# STM32G4_microcontroller_Power.net
KiCad netlist of a schematic drawn in Altium Designer
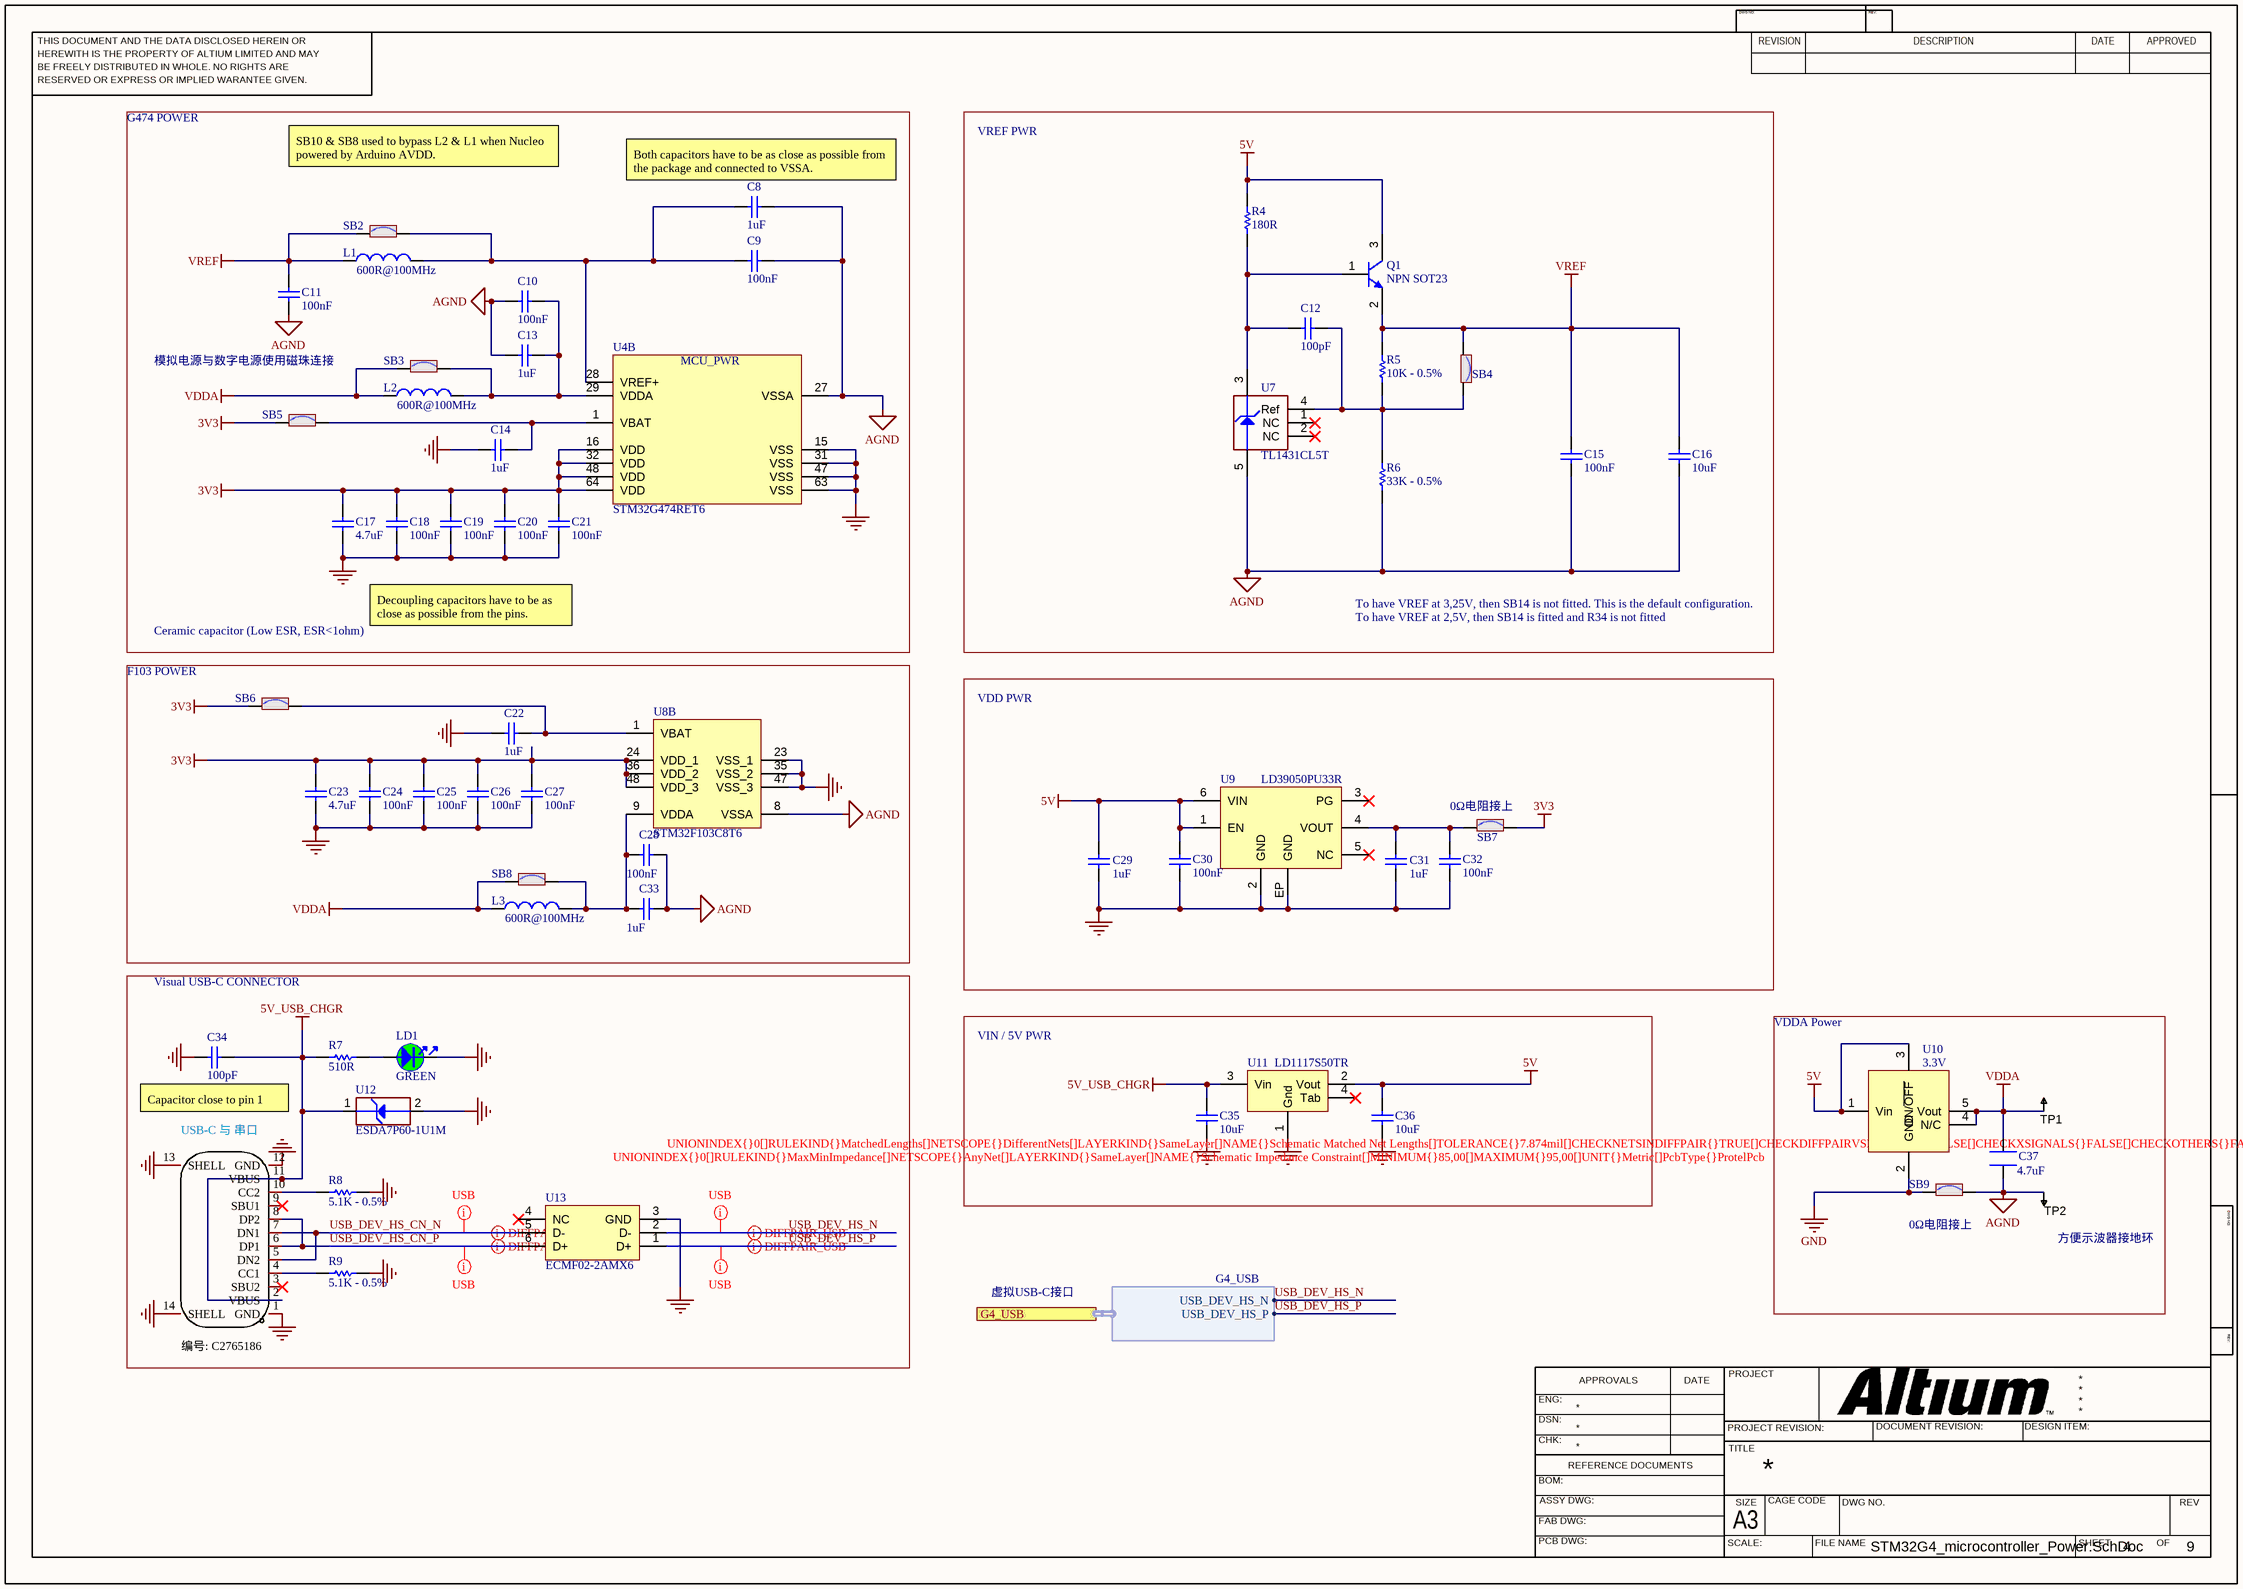
[diagram p0: STM32G4_microcontroller_Power.SchDoc]

(export (version "E")
  (design (tool "Eeschema 10.0.6"))
  (components
    (comp (ref "C8")
      (value "1uF")
      (footprint "C0603")
      (description "Capacitor, MLCC, 1uF, 16V, X5R, 10%, 0603, T=0,8mm")
      (fields
        (field (name "INTERNAL_PART_NUMBER") "MCD-00010")
        (field (name "MANUFACTURER_PART_NUMBER") "CC0603KRX5R7BB105")
        (field (name "PROVIDED_BY") "Subcon")
      )
      (libsource (lib "MCD_PARTS_database") (part "Capacitor"))
    )
    (comp (ref "C9")
      (value "100nF")
      (footprint "C0402")
      (description "Capacitor, MLCC, 100nF, 16V, X7R, 10%, 0402, T=0,5mm")
      (fields
        (field (name "INTERNAL_PART_NUMBER") "MCD-00102")
        (field (name "MANUFACTURER_PART_NUMBER") "CC0402KRX7R7BB104")
        (field (name "PROVIDED_BY") "Subcon")
      )
      (libsource (lib "MCD_PARTS_database") (part "Capacitor"))
    )
    (comp (ref "C10")
      (value "100nF")
      (footprint "C0402")
      (description "Capacitor, MLCC, 100nF, 16V, X7R, 10%, 0402, T=0,5mm")
      (fields
        (field (name "INTERNAL_PART_NUMBER") "MCD-00102")
        (field (name "MANUFACTURER_PART_NUMBER") "CC0402KRX7R7BB104")
        (field (name "PROVIDED_BY") "Subcon")
      )
      (libsource (lib "MCD_PARTS_database") (part "Capacitor"))
    )
    (comp (ref "C11")
      (value "100nF")
      (footprint "C0402")
      (description "Capacitor, MLCC, 100nF, 16V, X7R, 10%, 0402, T=0,5mm")
      (fields
        (field (name "INTERNAL_PART_NUMBER") "MCD-00102")
        (field (name "MANUFACTURER_PART_NUMBER") "CC0402KRX7R7BB104")
        (field (name "PROVIDED_BY") "Subcon")
      )
      (libsource (lib "MCD_PARTS_database") (part "Capacitor"))
    )
    (comp (ref "C12")
      (value "100pF")
      (footprint "C0603")
      (description "Capacitor,100pF,50V,X7R,10%,0603")
      (fields
        (field (name "INTERNAL_PART_NUMBER") "MCD-01101")
        (field (name "MANUFACTURER_PART_NUMBER") "06035C101JAT4A")
        (field (name "PROVIDED_BY") "SUBCO")
      )
      (libsource (lib "MCD_PARTS_database") (part "Capacitor"))
    )
    (comp (ref "C13")
      (value "1uF")
      (footprint "C0603")
      (description "Capacitor, MLCC, 1uF, 16V, X5R, 10%, 0603, T=0,8mm")
      (fields
        (field (name "INTERNAL_PART_NUMBER") "MCD-00010")
        (field (name "MANUFACTURER_PART_NUMBER") "CC0603KRX5R7BB105")
        (field (name "PROVIDED_BY") "Subcon")
      )
      (libsource (lib "MCD_PARTS_database") (part "Capacitor"))
    )
    (comp (ref "C14")
      (value "1uF")
      (footprint "C0603")
      (description "Capacitor, MLCC, 1uF, 16V, X5R, 10%, 0603, T=0,8mm")
      (fields
        (field (name "INTERNAL_PART_NUMBER") "MCD-00010")
        (field (name "MANUFACTURER_PART_NUMBER") "CC0603KRX5R7BB105")
        (field (name "PROVIDED_BY") "Subcon")
      )
      (libsource (lib "MCD_PARTS_database") (part "Capacitor"))
    )
    (comp (ref "C15")
      (value "100nF")
      (footprint "C0603")
      (description "Capacitor, MLCC, 100nF, 16V, X7R, 10%, 0603, T=0,8mm")
      (fields
        (field (name "INTERNAL_PART_NUMBER") "MCD-00211")
        (field (name "MANUFACTURER_PART_NUMBER") "CC0603KRX7R7BB104")
        (field (name "PROVIDED_BY") "SUBCO")
      )
      (libsource (lib "MCD_PARTS_database") (part "Capacitor"))
    )
    (comp (ref "C16")
      (value "10uF")
      (footprint "C0603")
      (description "Capacitor, MLCC, 10uF, 10V, X5R, 10%, 0603, T=0.8mm")
      (fields
        (field (name "INTERNAL_PART_NUMBER") "MCD-01124")
        (field (name "MANUFACTURER_PART_NUMBER") "GRM188R61A106KAAL")
        (field (name "PROVIDED_BY") "SUBCO")
      )
      (libsource (lib "MCD_PARTS_database") (part "Capacitor"))
    )
    (comp (ref "C17")
      (value "4.7uF")
      (footprint "C0603")
      (description "Capacitor, MLCC, 4.7uF, 16V, X5R, 10%, 0603, T=0.8mm")
      (fields
        (field (name "INTERNAL_PART_NUMBER") "MCD-00009")
        (field (name "MANUFACTURER_PART_NUMBER") "CC0603KRX5R7BB475")
        (field (name "PROVIDED_BY") "subcon")
      )
      (libsource (lib "MCD_PARTS_database") (part "Capacitor"))
    )
    (comp (ref "C18")
      (value "100nF")
      (footprint "C0402")
      (description "Capacitor, MLCC, 100nF, 16V, X7R, 10%, 0402, T=0,5mm")
      (fields
        (field (name "INTERNAL_PART_NUMBER") "MCD-00102")
        (field (name "MANUFACTURER_PART_NUMBER") "CC0402KRX7R7BB104")
        (field (name "PROVIDED_BY") "Subcon")
      )
      (libsource (lib "MCD_PARTS_database") (part "Capacitor"))
    )
    (comp (ref "C19")
      (value "100nF")
      (footprint "C0402")
      (description "Capacitor, MLCC, 100nF, 16V, X7R, 10%, 0402, T=0,5mm")
      (fields
        (field (name "INTERNAL_PART_NUMBER") "MCD-00102")
        (field (name "MANUFACTURER_PART_NUMBER") "CC0402KRX7R7BB104")
        (field (name "PROVIDED_BY") "Subcon")
      )
      (libsource (lib "MCD_PARTS_database") (part "Capacitor"))
    )
    (comp (ref "C20")
      (value "100nF")
      (footprint "C0402")
      (description "Capacitor, MLCC, 100nF, 16V, X7R, 10%, 0402, T=0,5mm")
      (fields
        (field (name "INTERNAL_PART_NUMBER") "MCD-00102")
        (field (name "MANUFACTURER_PART_NUMBER") "CC0402KRX7R7BB104")
        (field (name "PROVIDED_BY") "Subcon")
      )
      (libsource (lib "MCD_PARTS_database") (part "Capacitor"))
    )
    (comp (ref "C21")
      (value "100nF")
      (footprint "C0402")
      (description "Capacitor, MLCC, 100nF, 16V, X7R, 10%, 0402, T=0,5mm")
      (fields
        (field (name "INTERNAL_PART_NUMBER") "MCD-00102")
        (field (name "MANUFACTURER_PART_NUMBER") "CC0402KRX7R7BB104")
        (field (name "PROVIDED_BY") "Subcon")
      )
      (libsource (lib "MCD_PARTS_database") (part "Capacitor"))
    )
    (comp (ref "C22")
      (value "1uF")
      (footprint "C0603")
      (description "Capacitor, MLCC, 1uF, 16V, X5R, 10%, 0603, T=0,8mm")
      (fields
        (field (name "INTERNAL_PART_NUMBER") "MCD-00010")
        (field (name "MANUFACTURER_PART_NUMBER") "CC0603KRX5R7BB105")
        (field (name "PROVIDED_BY") "Subcon")
      )
      (libsource (lib "MCD_PARTS_database") (part "Capacitor"))
    )
    (comp (ref "C23")
      (value "4.7uF")
      (footprint "C0603")
      (description "Capacitor, MLCC, 4.7uF, 16V, X5R, 10%, 0603, T=0.8mm")
      (fields
        (field (name "INTERNAL_PART_NUMBER") "MCD-00009")
        (field (name "MANUFACTURER_PART_NUMBER") "CC0603KRX5R7BB475")
        (field (name "PROVIDED_BY") "subcon")
      )
      (libsource (lib "MCD_PARTS_database") (part "Capacitor"))
    )
    (comp (ref "C24")
      (value "100nF")
      (footprint "C0402")
      (description "Capacitor, MLCC, 100nF, 16V, X7R, 10%, 0402, T=0,5mm")
      (fields
        (field (name "INTERNAL_PART_NUMBER") "MCD-00102")
        (field (name "MANUFACTURER_PART_NUMBER") "CC0402KRX7R7BB104")
        (field (name "PROVIDED_BY") "Subcon")
      )
      (libsource (lib "MCD_PARTS_database") (part "Capacitor"))
    )
    (comp (ref "C25")
      (value "100nF")
      (footprint "C0402")
      (description "Capacitor, MLCC, 100nF, 16V, X7R, 10%, 0402, T=0,5mm")
      (fields
        (field (name "INTERNAL_PART_NUMBER") "MCD-00102")
        (field (name "MANUFACTURER_PART_NUMBER") "CC0402KRX7R7BB104")
        (field (name "PROVIDED_BY") "Subcon")
      )
      (libsource (lib "MCD_PARTS_database") (part "Capacitor"))
    )
    (comp (ref "C26")
      (value "100nF")
      (footprint "C0402")
      (description "Capacitor, MLCC, 100nF, 16V, X7R, 10%, 0402, T=0,5mm")
      (fields
        (field (name "INTERNAL_PART_NUMBER") "MCD-00102")
        (field (name "MANUFACTURER_PART_NUMBER") "CC0402KRX7R7BB104")
        (field (name "PROVIDED_BY") "Subcon")
      )
      (libsource (lib "MCD_PARTS_database") (part "Capacitor"))
    )
    (comp (ref "C27")
      (value "100nF")
      (footprint "C0402")
      (description "Capacitor, MLCC, 100nF, 16V, X7R, 10%, 0402, T=0,5mm")
      (fields
        (field (name "INTERNAL_PART_NUMBER") "MCD-00102")
        (field (name "MANUFACTURER_PART_NUMBER") "CC0402KRX7R7BB104")
        (field (name "PROVIDED_BY") "Subcon")
      )
      (libsource (lib "MCD_PARTS_database") (part "Capacitor"))
    )
    (comp (ref "C28")
      (value "100nF")
      (footprint "C0402")
      (description "Capacitor, MLCC, 100nF, 16V, X7R, 10%, 0402, T=0,5mm")
      (fields
        (field (name "INTERNAL_PART_NUMBER") "MCD-00102")
        (field (name "MANUFACTURER_PART_NUMBER") "CC0402KRX7R7BB104")
        (field (name "PROVIDED_BY") "Subcon")
      )
      (libsource (lib "MCD_PARTS_database") (part "Capacitor"))
    )
    (comp (ref "C29")
      (value "1uF")
      (footprint "C0603")
      (description "Capacitor, MLCC, 1uF, 16V, X5R, 10%, 0603, T=0,8mm")
      (fields
        (field (name "INTERNAL_PART_NUMBER") "MCD-00010")
        (field (name "MANUFACTURER_PART_NUMBER") "CC0603KRX5R7BB105")
        (field (name "PROVIDED_BY") "Subcon")
      )
      (libsource (lib "MCD_PARTS_database") (part "Capacitor"))
    )
    (comp (ref "C30")
      (value "100nF")
      (footprint "C0402")
      (description "Capacitor, MLCC, 100nF, 16V, X7R, 10%, 0402, T=0,5mm")
      (fields
        (field (name "INTERNAL_PART_NUMBER") "MCD-00102")
        (field (name "MANUFACTURER_PART_NUMBER") "CC0402KRX7R7BB104")
        (field (name "PROVIDED_BY") "Subcon")
      )
      (libsource (lib "MCD_PARTS_database") (part "Capacitor"))
    )
    (comp (ref "C31")
      (value "1uF")
      (footprint "C0603")
      (description "Capacitor, MLCC, 1uF, 16V, X5R, 10%, 0603, T=0,8mm")
      (fields
        (field (name "INTERNAL_PART_NUMBER") "MCD-00010")
        (field (name "MANUFACTURER_PART_NUMBER") "CC0603KRX5R7BB105")
        (field (name "PROVIDED_BY") "Subcon")
      )
      (libsource (lib "MCD_PARTS_database") (part "Capacitor"))
    )
    (comp (ref "C32")
      (value "100nF")
      (footprint "C0402")
      (description "Capacitor, MLCC, 100nF, 16V, X7R, 10%, 0402, T=0,5mm")
      (fields
        (field (name "INTERNAL_PART_NUMBER") "MCD-00102")
        (field (name "MANUFACTURER_PART_NUMBER") "CC0402KRX7R7BB104")
        (field (name "PROVIDED_BY") "Subcon")
      )
      (libsource (lib "MCD_PARTS_database") (part "Capacitor"))
    )
    (comp (ref "C33")
      (value "1uF")
      (footprint "C0603")
      (description "Capacitor, MLCC, 1uF, 16V, X5R, 10%, 0603, T=0,8mm")
      (fields
        (field (name "INTERNAL_PART_NUMBER") "MCD-00010")
        (field (name "MANUFACTURER_PART_NUMBER") "CC0603KRX5R7BB105")
        (field (name "PROVIDED_BY") "Subcon")
      )
      (libsource (lib "MCD_PARTS_database") (part "Capacitor"))
    )
    (comp (ref "C34")
      (value "100pF")
      (footprint "C0402")
      (description "Capacitor, MLCC, 100pF, 50V, NPO, 5%, 0402, T=0,5mm")
      (fields
        (field (name "INTERNAL_PART_NUMBER") "MCD-00205")
        (field (name "MANUFACTURER_PART_NUMBER") "CC0402JRNPO9BN101")
        (field (name "PROVIDED_BY") "Subcon")
      )
      (libsource (lib "MCD_PARTS_database") (part "Capacitor"))
    )
    (comp (ref "C35")
      (value "10uF")
      (footprint "C0805")
      (description "Capacitor, MLCC, 10uF, 25V, X5R, 10%, 0805, T=0,85mm")
      (fields
        (field (name "INTERNAL_PART_NUMBER") "MCD-00014")
        (field (name "MANUFACTURER_PART_NUMBER") "CC0805KRX5R8BB106")
        (field (name "PROVIDED_BY") "SUBCO")
      )
      (libsource (lib "MCD_PARTS_database") (part "Capacitor"))
    )
    (comp (ref "C36")
      (value "10uF")
      (footprint "C0805")
      (description "Capacitor, MLCC, 10uF, 25V, X5R, 10%, 0805, T=0,85mm")
      (fields
        (field (name "INTERNAL_PART_NUMBER") "MCD-00014")
        (field (name "MANUFACTURER_PART_NUMBER") "CC0805KRX5R8BB106")
        (field (name "PROVIDED_BY") "SUBCO")
      )
      (libsource (lib "MCD_PARTS_database") (part "Capacitor"))
    )
    (comp (ref "C37")
      (value "4.7uF")
      (footprint "CAPC2012X09N")
      (description "CAP CER 4.7UF 35V X5R 0805")
      (fields
        (field (name "MANUFACTURER") "Murata Electronics North America")
        (field (name "TOLERANCE") "±10%")
      )
      (libsource (lib "CustomComponents") (part "GRM219R6YA475KA73D"))
    )
    (comp (ref "L1")
      (value "600R@100MHz")
      (footprint "L0603")
      (description "SMD Chip ferrite bead, 600R@100MHz +/-25%, 350mA, 500mohm DC, 0603, T=0.8mm")
      (fields
        (field (name "INTERNAL_PART_NUMBER") "MCD-00047")
        (field (name "MANUFACTURER_PART_NUMBER") "FCM1608KF-601T03")
        (field (name "PROVIDED_BY") "SUBCO")
      )
      (libsource (lib "MCD_PARTS_database") (part "BEAD"))
    )
    (comp (ref "L2")
      (value "600R@100MHz")
      (footprint "L0603")
      (description "SMD Chip ferrite bead, 600R@100MHz +/-25%, 350mA, 500mohm DC, 0603, T=0.8mm")
      (fields
        (field (name "INTERNAL_PART_NUMBER") "MCD-00047")
        (field (name "MANUFACTURER_PART_NUMBER") "FCM1608KF-601T03")
        (field (name "PROVIDED_BY") "SUBCO")
      )
      (libsource (lib "MCD_PARTS_database") (part "BEAD"))
    )
    (comp (ref "L3")
      (value "600R@100MHz")
      (footprint "L0603")
      (description "SMD Chip ferrite bead, 600R@100MHz +/-25%, 350mA, 500mohm DC, 0603, T=0.8mm")
      (fields
        (field (name "INTERNAL_PART_NUMBER") "MCD-00047")
        (field (name "MANUFACTURER_PART_NUMBER") "FCM1608KF-601T03")
        (field (name "PROVIDED_BY") "SUBCO")
      )
      (libsource (lib "MCD_PARTS_database") (part "BEAD"))
    )
    (comp (ref "LD1")
      (value "GREEN")
      (footprint "LED_0603_GREEN")
      (description "LED, Green, 0603")
      (fields
        (field (name "INTERNAL_PART_NUMBER") "MCD-00050")
        (field (name "MANUFACTURER_PART_NUMBER") "19-213SYGC/S530-E2/TR8")
        (field (name "PROVIDED_BY") "SUBCO")
      )
      (libsource (lib "MCD_PARTS_database") (part "LED_green"))
    )
    (comp (ref "Q1")
      (value "NPN SOT23")
      (footprint "NPN_SOT23")
      (description "NPN Bipolar Transistor")
      (fields
        (field (name "INTERNAL_PART_NUMBER") "MCD-00073")
        (field (name "MANUFACTURER_PART_NUMBER") "BSR14")
        (field (name "PROVIDED_BY") "SUBCO")
      )
      (libsource (lib "MCD_PARTS_database") (part "9013-SOT23"))
    )
    (comp (ref "R4")
      (value "180R")
      (footprint "R0603")
      (description "Resistor,180R,0603,1%,1/10W")
      (fields
        (field (name "INTERNAL_PART_NUMBER") "MCD-00342")
        (field (name "MANUFACTURER_PART_NUMBER") "RC0603FR-07180RL")
        (field (name "PROVIDED_BY") "SUBCO")
      )
      (libsource (lib "MCD_PARTS_database") (part "Resistor"))
    )
    (comp (ref "R5")
      (value "10K - 0.5%")
      (footprint "R0603")
      (description "resistor, 10K, 0603, 0.5%, 1/10W")
      (fields
        (field (name "INTERNAL_PART_NUMBER") "MCD-01215")
        (field (name "MANUFACTURER_PART_NUMBER") "RC0603DR-0710KL")
        (field (name "PROVIDED_BY") "SUBCO")
      )
      (libsource (lib "MCD_PARTS_database") (part "Resistor"))
    )
    (comp (ref "R6")
      (value "33K - 0.5%")
      (footprint "R0603")
      (description "Resistor,33K,0603,0.5%,1/10W")
      (fields
        (field (name "INTERNAL_PART_NUMBER") "MCD-01209")
        (field (name "MANUFACTURER_PART_NUMBER") "RC0603DR-0733KL")
        (field (name "PROVIDED_BY") "SUBCO")
      )
      (libsource (lib "MCD_PARTS_database") (part "Resistor"))
    )
    (comp (ref "R7")
      (value "510R")
      (footprint "R0603")
      (description "Resistor,510R,0603,1%,1/10W")
      (fields
        (field (name "INTERNAL_PART_NUMBER") "MCD-00225")
        (field (name "MANUFACTURER_PART_NUMBER") "RC0603FR-07510RL")
        (field (name "PROVIDED_BY") "SUBCO")
      )
      (libsource (lib "MCD_PARTS_database") (part "Resistor"))
    )
    (comp (ref "R8")
      (value "5.1K - 0.5%")
      (footprint "R0603")
      (description "Resistor,5.1K,0603,0.5%,1/10W")
      (fields
        (field (name "INTERNAL_PART_NUMBER") "MCD-01209")
        (field (name "MANUFACTURER_PART_NUMBER") "RC0603DR-0733KL")
        (field (name "PROVIDED_BY") "SUBCO")
      )
      (libsource (lib "MCD_PARTS_database") (part "Resistor"))
    )
    (comp (ref "R9")
      (value "5.1K - 0.5%")
      (footprint "R0603")
      (description "Resistor,5.1K,0603,0.5%,1/10W")
      (fields
        (field (name "INTERNAL_PART_NUMBER") "MCD-01209")
        (field (name "MANUFACTURER_PART_NUMBER") "RC0603DR-0733KL")
        (field (name "PROVIDED_BY") "SUBCO")
      )
      (libsource (lib "MCD_PARTS_database") (part "Resistor"))
    )
    (comp (ref "SB2")
      (value "~")
      (footprint "SOLDER-BRIDGE_R0603-0R")
      (description "Solder Bridge ON")
      (fields
        (field (name "INTERNAL_PART_NUMBER") "MCD-00071")
        (field (name "MANUFACTURER_PART_NUMBER") "RC0603JR-070RL")
        (field (name "PROVIDED_BY") "SUBCO")
      )
      (libsource (lib "MCD_PARTS_database") (part "SB_ON"))
    )
    (comp (ref "SB3")
      (value "~")
      (footprint "SOLDER-BRIDGE_R0603-0R")
      (description "Solder Bridge ON")
      (fields
        (field (name "INTERNAL_PART_NUMBER") "MCD-00071")
        (field (name "MANUFACTURER_PART_NUMBER") "RC0603JR-070RL")
        (field (name "PROVIDED_BY") "SUBCO")
      )
      (libsource (lib "MCD_PARTS_database") (part "SB_ON"))
    )
    (comp (ref "SB4")
      (value "~")
      (footprint "SOLDER-BRIDGE_R0603-0R")
      (description "Solder Bridge ON")
      (fields
        (field (name "INTERNAL_PART_NUMBER") "MCD-00071")
        (field (name "MANUFACTURER_PART_NUMBER") "RC0603JR-070RL")
        (field (name "PROVIDED_BY") "SUBCO")
      )
      (libsource (lib "") (part "SB_ON_1"))
    )
    (comp (ref "SB5")
      (value "~")
      (footprint "SOLDER-BRIDGE_R0603-0R")
      (description "Solder Bridge ON")
      (fields
        (field (name "INTERNAL_PART_NUMBER") "MCD-00071")
        (field (name "MANUFACTURER_PART_NUMBER") "RC0603JR-070RL")
        (field (name "PROVIDED_BY") "SUBCO")
      )
      (libsource (lib "MCD_PARTS_database") (part "SB_ON"))
    )
    (comp (ref "SB6")
      (value "~")
      (footprint "SOLDER-BRIDGE_R0603-0R")
      (description "Solder Bridge ON")
      (fields
        (field (name "INTERNAL_PART_NUMBER") "MCD-00071")
        (field (name "MANUFACTURER_PART_NUMBER") "RC0603JR-070RL")
        (field (name "PROVIDED_BY") "SUBCO")
      )
      (libsource (lib "MCD_PARTS_database") (part "SB_ON"))
    )
    (comp (ref "SB7")
      (value "~")
      (footprint "SOLDER-BRIDGE_R0603-0R")
      (description "Solder Bridge ON")
      (fields
        (field (name "INTERNAL_PART_NUMBER") "MCD-00071")
        (field (name "MANUFACTURER_PART_NUMBER") "RC0603JR-070RL")
        (field (name "PROVIDED_BY") "SUBCO")
      )
      (libsource (lib "MCD_PARTS_database") (part "SB_ON"))
    )
    (comp (ref "SB8")
      (value "~")
      (footprint "SOLDER-BRIDGE_R0603-0R")
      (description "Solder Bridge ON")
      (fields
        (field (name "INTERNAL_PART_NUMBER") "MCD-00071")
        (field (name "MANUFACTURER_PART_NUMBER") "RC0603JR-070RL")
        (field (name "PROVIDED_BY") "SUBCO")
      )
      (libsource (lib "MCD_PARTS_database") (part "SB_ON"))
    )
    (comp (ref "SB9")
      (value "~")
      (footprint "SOLDER-BRIDGE_R0603-0R")
      (description "Solder Bridge ON")
      (fields
        (field (name "INTERNAL_PART_NUMBER") "MCD-00071")
        (field (name "MANUFACTURER_PART_NUMBER") "RC0603JR-070RL")
        (field (name "PROVIDED_BY") "SUBCO")
      )
      (libsource (lib "MCD_PARTS_database") (part "SB_ON"))
    )
    (comp (ref "TP1")
      (value "TESTPOINT")
      (footprint "TP-R30")
      (description "SMD test pin")
      (libsource (lib "PBL - Test Points") (part "TESTPOINT"))
    )
    (comp (ref "TP2")
      (value "TESTPOINT")
      (footprint "TP-R30")
      (description "SMD test pin")
      (libsource (lib "PBL - Test Points") (part "TESTPOINT"))
    )
    (comp (ref "U4")
      (value "STM32G474RET6")
      (footprint "ICC_LQFP64_10X10_P050_SOCKET_YAMAICHI_IC149-064-069-B5_NM")
      (description "STM32G474, LQFP64 package,  3D IC footprint with 2D socket footprint.")
      (fields
        (field (name "INTERNAL_PART_NUMBER") "MCD-01243")
        (field (name "MANUFACTURER") "STMICROELECTRONICS")
        (field (name "PROVIDED_BY") "SUBCO with ST control")
      )
      (libsource (lib "MCD_PARTS_database") (part "STM32G4xx_LQFP64"))
    )
    (comp (ref "U7")
      (value "TL1431CL5T")
      (footprint "ICC_SOT23-5L_H1P45")
      (description "Programmable voltage reference with 0.4% voltage precision")
      (fields
        (field (name "INTERNAL_PART_NUMBER") "MCD-01802")
        (field (name "MANUFACTURER") "STMICROELECTRONICS")
        (field (name "PROVIDED_BY") "SUBCO with ST control")
      )
      (libsource (lib "MCD_PARTS_database") (part "TL1431ACL5T"))
    )
    (comp (ref "U8")
      (value "STM32F103C8T6")
      (footprint "STM-LQFP48_L")
      (libsource (lib "Altium Content Vault") (part "MC-ARM-STM32F103X8_B-SQ48"))
    )
    (comp (ref "U9")
      (value "LD39050PU33R")
      (footprint "ICC_DFN6-EPAD_3X3_P095")
      (description "Low quiescent current and low noise voltage regulators")
      (fields
        (field (name "INTERNAL_PART_NUMBER") "MCD-00215")
        (field (name "MANUFACTURER") "STMICROELECTRONICS")
        (field (name "PROVIDED_BY") "SUBCO with ST control")
      )
      (libsource (lib "MCD_PARTS_database") (part "LD39050PU33R"))
    )
    (comp (ref "U10")
      (value "3.3V")
      (footprint "SOT23-5")
      (description "IC REG LDO 3.3V 0.25A SOT23-5")
      (fields (field (name "MANUFACTURER") "Texas Instruments"))
      (libsource (lib "CustomComponents") (part "LP5907MFX-3.3/NOPB"))
    )
    (comp (ref "U11")
      (value "LD1117S50TR")
      (footprint "REG_SOT223-TAB")
      (description "IC REG LDO 5V 0.8A SOT223")
      (fields
        (field (name "INTERNAL_PART_NUMBER") "MCD-00088")
        (field (name "MANUFACTURER") "STMICROELECTRONICS")
        (field (name "PROVIDED_BY") "SUBCO with ST control")
      )
      (libsource (lib "MCD_PARTS_database") (part "LD1117S50TR"))
    )
    (comp (ref "U12")
      (value "ESDA7P60-1U1M")
      (footprint "ESD_QFN2_1P6X1_P125")
      (description "High power transient voltage suppressor, 7V breakdown")
      (fields
        (field (name "INTERNAL_PART_NUMBER") "MCD-00251")
        (field (name "MANUFACTURER") "STMICROELECTRONICS")
        (field (name "PROVIDED_BY") "Subcon")
      )
      (libsource (lib "MCD_PARTS_database") (part "ESD-TRANSIL"))
    )
    (comp (ref "U13")
      (value "ECMF02-2AMX6")
      (footprint "ESD_QFN-6L_1P7X1P5_P050")
      (description "Common mode filter with ESD protection for USB 2.0 interface")
      (fields
        (field (name "INTERNAL_PART_NUMBER") "MCD-00649")
        (field (name "MANUFACTURER") "STMICROELECTRONICS")
        (field (name "PROVIDED_BY") "Subcon")
      )
      (libsource (lib "MCD_PARTS_database") (part "ECMF02-2AMX6"))
    )
    (comp (ref "USB1")
      (value "TYPE-C 16PIN 2MD(073)")
      (footprint "USB-C-SMD_TYPE-C-6PIN-2MD-073")
      (fields (field (name "MANUFACTURER") "SHOU HAN(首韩)"))
      (libsource (lib "mb1367") (part "TYPE-C 16PIN 2MD(073)"))
    )
  )
  (nets
    (net (code "2") (name "/USB_DEV_HS_CN_N") (class "Default")
      (node (ref "U13") (pin "5") (pinfunction "D-_5") (pintype "passive"))
      (node (ref "USB1") (pin "5") (pinfunction "DN2_5") (pintype "passive"))
      (node (ref "USB1") (pin "7") (pinfunction "DN1_7") (pintype "passive"))
    )
    (net (code "3") (name "/USB_DEV_HS_CN_P") (class "Default")
      (node (ref "U13") (pin "6") (pinfunction "D+_6") (pintype "passive"))
      (node (ref "USB1") (pin "6") (pinfunction "DP1_6") (pintype "passive"))
      (node (ref "USB1") (pin "8") (pinfunction "DP2_8") (pintype "passive"))
    )
    (net (code "4") (name "/USB_DEV_HS_N") (class "Default")
      (node (ref "U13") (pin "2") (pinfunction "D-_2") (pintype "passive"))
    )
    (net (code "5") (name "/USB_DEV_HS_P") (class "Default")
      (node (ref "U13") (pin "1") (pinfunction "D+_1") (pintype "passive"))
    )
    (net (code "7") (name "3V3") (class "Default")
      (node (ref "C17") (pin "2") (pinfunction "2_2") (pintype "passive"))
      (node (ref "C18") (pin "2") (pinfunction "2_2") (pintype "passive"))
      (node (ref "C19") (pin "2") (pinfunction "2_2") (pintype "passive"))
      (node (ref "C20") (pin "2") (pinfunction "2_2") (pintype "passive"))
      (node (ref "C21") (pin "2") (pinfunction "2_2") (pintype "passive"))
      (node (ref "C23") (pin "2") (pinfunction "2_2") (pintype "passive"))
      (node (ref "C24") (pin "2") (pinfunction "2_2") (pintype "passive"))
      (node (ref "C25") (pin "2") (pinfunction "2_2") (pintype "passive"))
      (node (ref "C26") (pin "2") (pinfunction "2_2") (pintype "passive"))
      (node (ref "C27") (pin "2") (pinfunction "2_2") (pintype "passive"))
      (node (ref "SB5") (pin "1") (pinfunction "1_1") (pintype "passive"))
      (node (ref "SB6") (pin "1") (pinfunction "1_1") (pintype "passive"))
      (node (ref "SB7") (pin "2") (pinfunction "2_2") (pintype "passive"))
      (node (ref "U4") (pin "16") (pinfunction "VDD_16") (pintype "passive"))
      (node (ref "U4") (pin "32") (pinfunction "VDD_32") (pintype "passive"))
      (node (ref "U4") (pin "48") (pinfunction "VDD_48") (pintype "passive"))
      (node (ref "U4") (pin "64") (pinfunction "VDD_64") (pintype "passive"))
      (node (ref "U8") (pin "24") (pinfunction "VDD_1_24") (pintype "power_in"))
      (node (ref "U8") (pin "36") (pinfunction "VDD_2_36") (pintype "power_in"))
      (node (ref "U8") (pin "48") (pinfunction "VDD_3_48") (pintype "power_in"))
    )
    (net (code "8") (name "5V") (class "Default")
      (node (ref "C29") (pin "2") (pinfunction "2_2") (pintype "passive"))
      (node (ref "C30") (pin "2") (pinfunction "2_2") (pintype "passive"))
      (node (ref "C36") (pin "2") (pinfunction "2_2") (pintype "passive"))
      (node (ref "Q1") (pin "3") (pinfunction "C_3") (pintype "passive"))
      (node (ref "R4") (pin "2") (pinfunction "2_2") (pintype "passive"))
      (node (ref "U10") (pin "1") (pinfunction "Vin_1") (pintype "passive"))
      (node (ref "U10") (pin "3") (pinfunction "ON/~{OFF}_3") (pintype "passive"))
      (node (ref "U11") (pin "2") (pinfunction "Vout_2") (pintype "passive"))
      (node (ref "U9") (pin "1") (pinfunction "EN_1") (pintype "passive"))
      (node (ref "U9") (pin "6") (pinfunction "VIN_6") (pintype "passive"))
    )
    (net (code "9") (name "5V_USB_CHGR") (class "Default")
      (node (ref "C34") (pin "2") (pinfunction "2_2") (pintype "passive"))
      (node (ref "C35") (pin "2") (pinfunction "2_2") (pintype "passive"))
      (node (ref "R7") (pin "2") (pinfunction "2_2") (pintype "passive"))
      (node (ref "U11") (pin "3") (pinfunction "Vin_3") (pintype "passive"))
      (node (ref "U12") (pin "1") (pinfunction "IO1_1") (pintype "passive"))
      (node (ref "USB1") (pin "11") (pinfunction "VBUS_11") (pintype "passive"))
      (node (ref "USB1") (pin "2") (pinfunction "VBUS_2") (pintype "passive"))
    )
    (net (code "10") (name "AGND") (class "Default")
      (node (ref "C10") (pin "1") (pinfunction "1_1") (pintype "passive"))
      (node (ref "C11") (pin "1") (pinfunction "1_1") (pintype "passive"))
      (node (ref "C13") (pin "1") (pinfunction "1_1") (pintype "passive"))
      (node (ref "C15") (pin "1") (pinfunction "1_1") (pintype "passive"))
      (node (ref "C16") (pin "1") (pinfunction "1_1") (pintype "passive"))
      (node (ref "C28") (pin "1") (pinfunction "1_1") (pintype "passive"))
      (node (ref "C33") (pin "1") (pinfunction "1_1") (pintype "passive"))
      (node (ref "C37") (pin "1") (pinfunction "1_1") (pintype "passive"))
      (node (ref "C8") (pin "2") (pinfunction "2_2") (pintype "passive"))
      (node (ref "C9") (pin "2") (pinfunction "2_2") (pintype "passive"))
      (node (ref "R6") (pin "1") (pinfunction "1_1") (pintype "passive"))
      (node (ref "SB9") (pin "2") (pinfunction "2_2") (pintype "passive"))
      (node (ref "TP2") (pin "1") (pintype "passive"))
      (node (ref "U4") (pin "27") (pinfunction "VSSA_27") (pintype "passive"))
      (node (ref "U7") (pin "5") (pinfunction "Anode_5") (pintype "passive"))
      (node (ref "U8") (pin "8") (pinfunction "VSSA_8") (pintype "power_in"))
    )
    (net (code "11") (name "GND") (class "Default")
      (node (ref "C14") (pin "1") (pinfunction "1_1") (pintype "passive"))
      (node (ref "C17") (pin "1") (pinfunction "1_1") (pintype "passive"))
      (node (ref "C18") (pin "1") (pinfunction "1_1") (pintype "passive"))
      (node (ref "C19") (pin "1") (pinfunction "1_1") (pintype "passive"))
      (node (ref "C20") (pin "1") (pinfunction "1_1") (pintype "passive"))
      (node (ref "C21") (pin "1") (pinfunction "1_1") (pintype "passive"))
      (node (ref "C22") (pin "1") (pinfunction "1_1") (pintype "passive"))
      (node (ref "C23") (pin "1") (pinfunction "1_1") (pintype "passive"))
      (node (ref "C24") (pin "1") (pinfunction "1_1") (pintype "passive"))
      (node (ref "C25") (pin "1") (pinfunction "1_1") (pintype "passive"))
      (node (ref "C26") (pin "1") (pinfunction "1_1") (pintype "passive"))
      (node (ref "C27") (pin "1") (pinfunction "1_1") (pintype "passive"))
      (node (ref "C29") (pin "1") (pinfunction "1_1") (pintype "passive"))
      (node (ref "C30") (pin "1") (pinfunction "1_1") (pintype "passive"))
      (node (ref "C31") (pin "1") (pinfunction "1_1") (pintype "passive"))
      (node (ref "C32") (pin "1") (pinfunction "1_1") (pintype "passive"))
      (node (ref "C34") (pin "1") (pinfunction "1_1") (pintype "passive"))
      (node (ref "C35") (pin "1") (pinfunction "1_1") (pintype "passive"))
      (node (ref "C36") (pin "1") (pinfunction "1_1") (pintype "passive"))
      (node (ref "LD1") (pin "2") (pintype "passive"))
      (node (ref "R8") (pin "1") (pinfunction "1_1") (pintype "passive"))
      (node (ref "R9") (pin "1") (pinfunction "1_1") (pintype "passive"))
      (node (ref "SB9") (pin "1") (pinfunction "1_1") (pintype "passive"))
      (node (ref "U10") (pin "2") (pinfunction "GND_2") (pintype "passive"))
      (node (ref "U11") (pin "1") (pinfunction "Gnd_1") (pintype "passive"))
      (node (ref "U12") (pin "2") (pinfunction "GND_2") (pintype "passive"))
      (node (ref "U13") (pin "3") (pinfunction "GND_3") (pintype "passive"))
      (node (ref "U4") (pin "15") (pinfunction "VSS_15") (pintype "passive"))
      (node (ref "U4") (pin "31") (pinfunction "VSS_31") (pintype "passive"))
      (node (ref "U4") (pin "47") (pinfunction "VSS_47") (pintype "passive"))
      (node (ref "U4") (pin "63") (pinfunction "VSS_63") (pintype "passive"))
      (node (ref "U8") (pin "23") (pinfunction "VSS_1_23") (pintype "power_in"))
      (node (ref "U8") (pin "35") (pinfunction "VSS_2_35") (pintype "power_in"))
      (node (ref "U8") (pin "47") (pinfunction "VSS_3_47") (pintype "power_in"))
      (node (ref "U9") (pin "2") (pinfunction "GND_2") (pintype "passive"))
      (node (ref "U9") (pin "EP") (pinfunction "GND_EP") (pintype "passive"))
      (node (ref "USB1") (pin "1") (pinfunction "GND_1") (pintype "passive"))
      (node (ref "USB1") (pin "12") (pinfunction "GND_12") (pintype "passive"))
      (node (ref "USB1") (pin "13") (pinfunction "SHELL_13") (pintype "passive"))
      (node (ref "USB1") (pin "14") (pinfunction "SHELL_14") (pintype "passive"))
    )
    (net (code "12") (name "Net-(LD1-Pad1)") (class "Default")
      (node (ref "LD1") (pin "1") (pintype "passive"))
      (node (ref "R7") (pin "1") (pinfunction "1_1") (pintype "passive"))
    )
    (net (code "13") (name "Net-(Q1-B)") (class "Default")
      (node (ref "C12") (pin "1") (pinfunction "1_1") (pintype "passive"))
      (node (ref "Q1") (pin "1") (pinfunction "B_1") (pintype "passive"))
      (node (ref "R4") (pin "1") (pinfunction "1_1") (pintype "passive"))
      (node (ref "U7") (pin "3") (pinfunction "Cathode_3") (pintype "passive"))
    )
    (net (code "14") (name "Net-(U4B-VBAT)") (class "Default")
      (node (ref "C14") (pin "2") (pinfunction "2_2") (pintype "passive"))
      (node (ref "SB5") (pin "2") (pinfunction "2_2") (pintype "passive"))
      (node (ref "U4") (pin "1") (pinfunction "VBAT_1") (pintype "passive"))
    )
    (net (code "15") (name "Net-(U4B-VDDA)") (class "Default")
      (node (ref "C10") (pin "2") (pinfunction "2_2") (pintype "passive"))
      (node (ref "C13") (pin "2") (pinfunction "2_2") (pintype "passive"))
      (node (ref "L2") (pin "2") (pinfunction "2_2") (pintype "passive"))
      (node (ref "SB3") (pin "2") (pinfunction "2_2") (pintype "passive"))
      (node (ref "U4") (pin "29") (pinfunction "VDDA_29") (pintype "passive"))
    )
    (net (code "16") (name "Net-(U4B-VREF+)") (class "Default")
      (node (ref "C8") (pin "1") (pinfunction "1_1") (pintype "passive"))
      (node (ref "C9") (pin "1") (pinfunction "1_1") (pintype "passive"))
      (node (ref "L1") (pin "2") (pinfunction "2_2") (pintype "passive"))
      (node (ref "SB2") (pin "2") (pinfunction "2_2") (pintype "passive"))
      (node (ref "U4") (pin "28") (pinfunction "VREF+_28") (pintype "passive"))
    )
    (net (code "17") (name "Net-(U7-Ref)") (class "Default")
      (node (ref "C12") (pin "2") (pinfunction "2_2") (pintype "passive"))
      (node (ref "R5") (pin "1") (pinfunction "1_1") (pintype "passive"))
      (node (ref "R6") (pin "2") (pinfunction "2_2") (pintype "passive"))
      (node (ref "SB4") (pin "2") (pinfunction "2_2") (pintype "passive"))
      (node (ref "U7") (pin "4") (pinfunction "Ref_4") (pintype "passive"))
    )
    (net (code "18") (name "Net-(U8B-VBAT)") (class "Default")
      (node (ref "C22") (pin "2") (pinfunction "2_2") (pintype "passive"))
      (node (ref "SB6") (pin "2") (pinfunction "2_2") (pintype "passive"))
      (node (ref "U8") (pin "1") (pinfunction "VBAT_1") (pintype "power_in"))
    )
    (net (code "19") (name "Net-(U8B-VDDA)") (class "Default")
      (node (ref "C28") (pin "2") (pinfunction "2_2") (pintype "passive"))
      (node (ref "C33") (pin "2") (pinfunction "2_2") (pintype "passive"))
      (node (ref "L3") (pin "2") (pinfunction "2_2") (pintype "passive"))
      (node (ref "SB8") (pin "2") (pinfunction "2_2") (pintype "passive"))
      (node (ref "U8") (pin "9") (pinfunction "VDDA_9") (pintype "power_in"))
    )
    (net (code "20") (name "Net-(U9-VOUT)") (class "Default")
      (node (ref "C31") (pin "2") (pinfunction "2_2") (pintype "passive"))
      (node (ref "C32") (pin "2") (pinfunction "2_2") (pintype "passive"))
      (node (ref "SB7") (pin "1") (pinfunction "1_1") (pintype "passive"))
      (node (ref "U9") (pin "4") (pinfunction "VOUT_4") (pintype "passive"))
    )
    (net (code "21") (name "Net-(USB1-CC1)") (class "Default")
      (node (ref "R9") (pin "2") (pinfunction "2_2") (pintype "passive"))
      (node (ref "USB1") (pin "4") (pinfunction "CC1_4") (pintype "passive"))
    )
    (net (code "22") (name "Net-(USB1-CC2)") (class "Default")
      (node (ref "R8") (pin "2") (pinfunction "2_2") (pintype "passive"))
      (node (ref "USB1") (pin "10") (pinfunction "CC2_10") (pintype "passive"))
    )
    (net (code "23") (name "VDDA") (class "Default")
      (node (ref "C37") (pin "2") (pinfunction "2_2") (pintype "passive"))
      (node (ref "L2") (pin "1") (pinfunction "1_1") (pintype "passive"))
      (node (ref "L3") (pin "1") (pinfunction "1_1") (pintype "passive"))
      (node (ref "SB3") (pin "1") (pinfunction "1_1") (pintype "passive"))
      (node (ref "SB8") (pin "1") (pinfunction "1_1") (pintype "passive"))
      (node (ref "TP1") (pin "1") (pintype "passive"))
      (node (ref "U10") (pin "4") (pinfunction "N/C_4") (pintype "passive"))
      (node (ref "U10") (pin "5") (pinfunction "Vout_5") (pintype "passive"))
    )
    (net (code "24") (name "VREF") (class "Default")
      (node (ref "C11") (pin "2") (pinfunction "2_2") (pintype "passive"))
      (node (ref "C15") (pin "2") (pinfunction "2_2") (pintype "passive"))
      (node (ref "C16") (pin "2") (pinfunction "2_2") (pintype "passive"))
      (node (ref "L1") (pin "1") (pinfunction "1_1") (pintype "passive"))
      (node (ref "Q1") (pin "2") (pinfunction "E_2") (pintype "passive"))
      (node (ref "R5") (pin "2") (pinfunction "2_2") (pintype "passive"))
      (node (ref "SB2") (pin "1") (pinfunction "1_1") (pintype "passive"))
      (node (ref "SB4") (pin "1") (pinfunction "1_1") (pintype "passive"))
    )
    (net (code "25") (name "unconnected-(U7-NC-Pad1)") (class "Default")
      (node (ref "U7") (pin "1") (pinfunction "NC_1") (pintype "passive+no_connect"))
    )
    (net (code "26") (name "unconnected-(U7-NC-Pad2)") (class "Default")
      (node (ref "U7") (pin "2") (pinfunction "NC_2") (pintype "passive+no_connect"))
    )
    (net (code "27") (name "unconnected-(U9-NC-Pad5)") (class "Default")
      (node (ref "U9") (pin "5") (pinfunction "NC_5") (pintype "passive+no_connect"))
    )
    (net (code "28") (name "unconnected-(U9-PG-Pad3)") (class "Default")
      (node (ref "U9") (pin "3") (pinfunction "PG_3") (pintype "passive+no_connect"))
    )
    (net (code "29") (name "unconnected-(U11-Tab-Pad4)") (class "Default")
      (node (ref "U11") (pin "4") (pinfunction "Tab_4") (pintype "passive+no_connect"))
    )
    (net (code "30") (name "unconnected-(U13-NC-Pad4)") (class "Default")
      (node (ref "U13") (pin "4") (pinfunction "NC_4") (pintype "passive+no_connect"))
    )
    (net (code "31") (name "unconnected-(USB1-SBU1-Pad9)") (class "Default")
      (node (ref "USB1") (pin "9") (pinfunction "SBU1_9") (pintype "passive+no_connect"))
    )
    (net (code "32") (name "unconnected-(USB1-SBU2-Pad3)") (class "Default")
      (node (ref "USB1") (pin "3") (pinfunction "SBU2_3") (pintype "passive+no_connect"))
    )
  )
)
